# hdreader.net
KiCad netlist of a schematic drawn in EAGLE
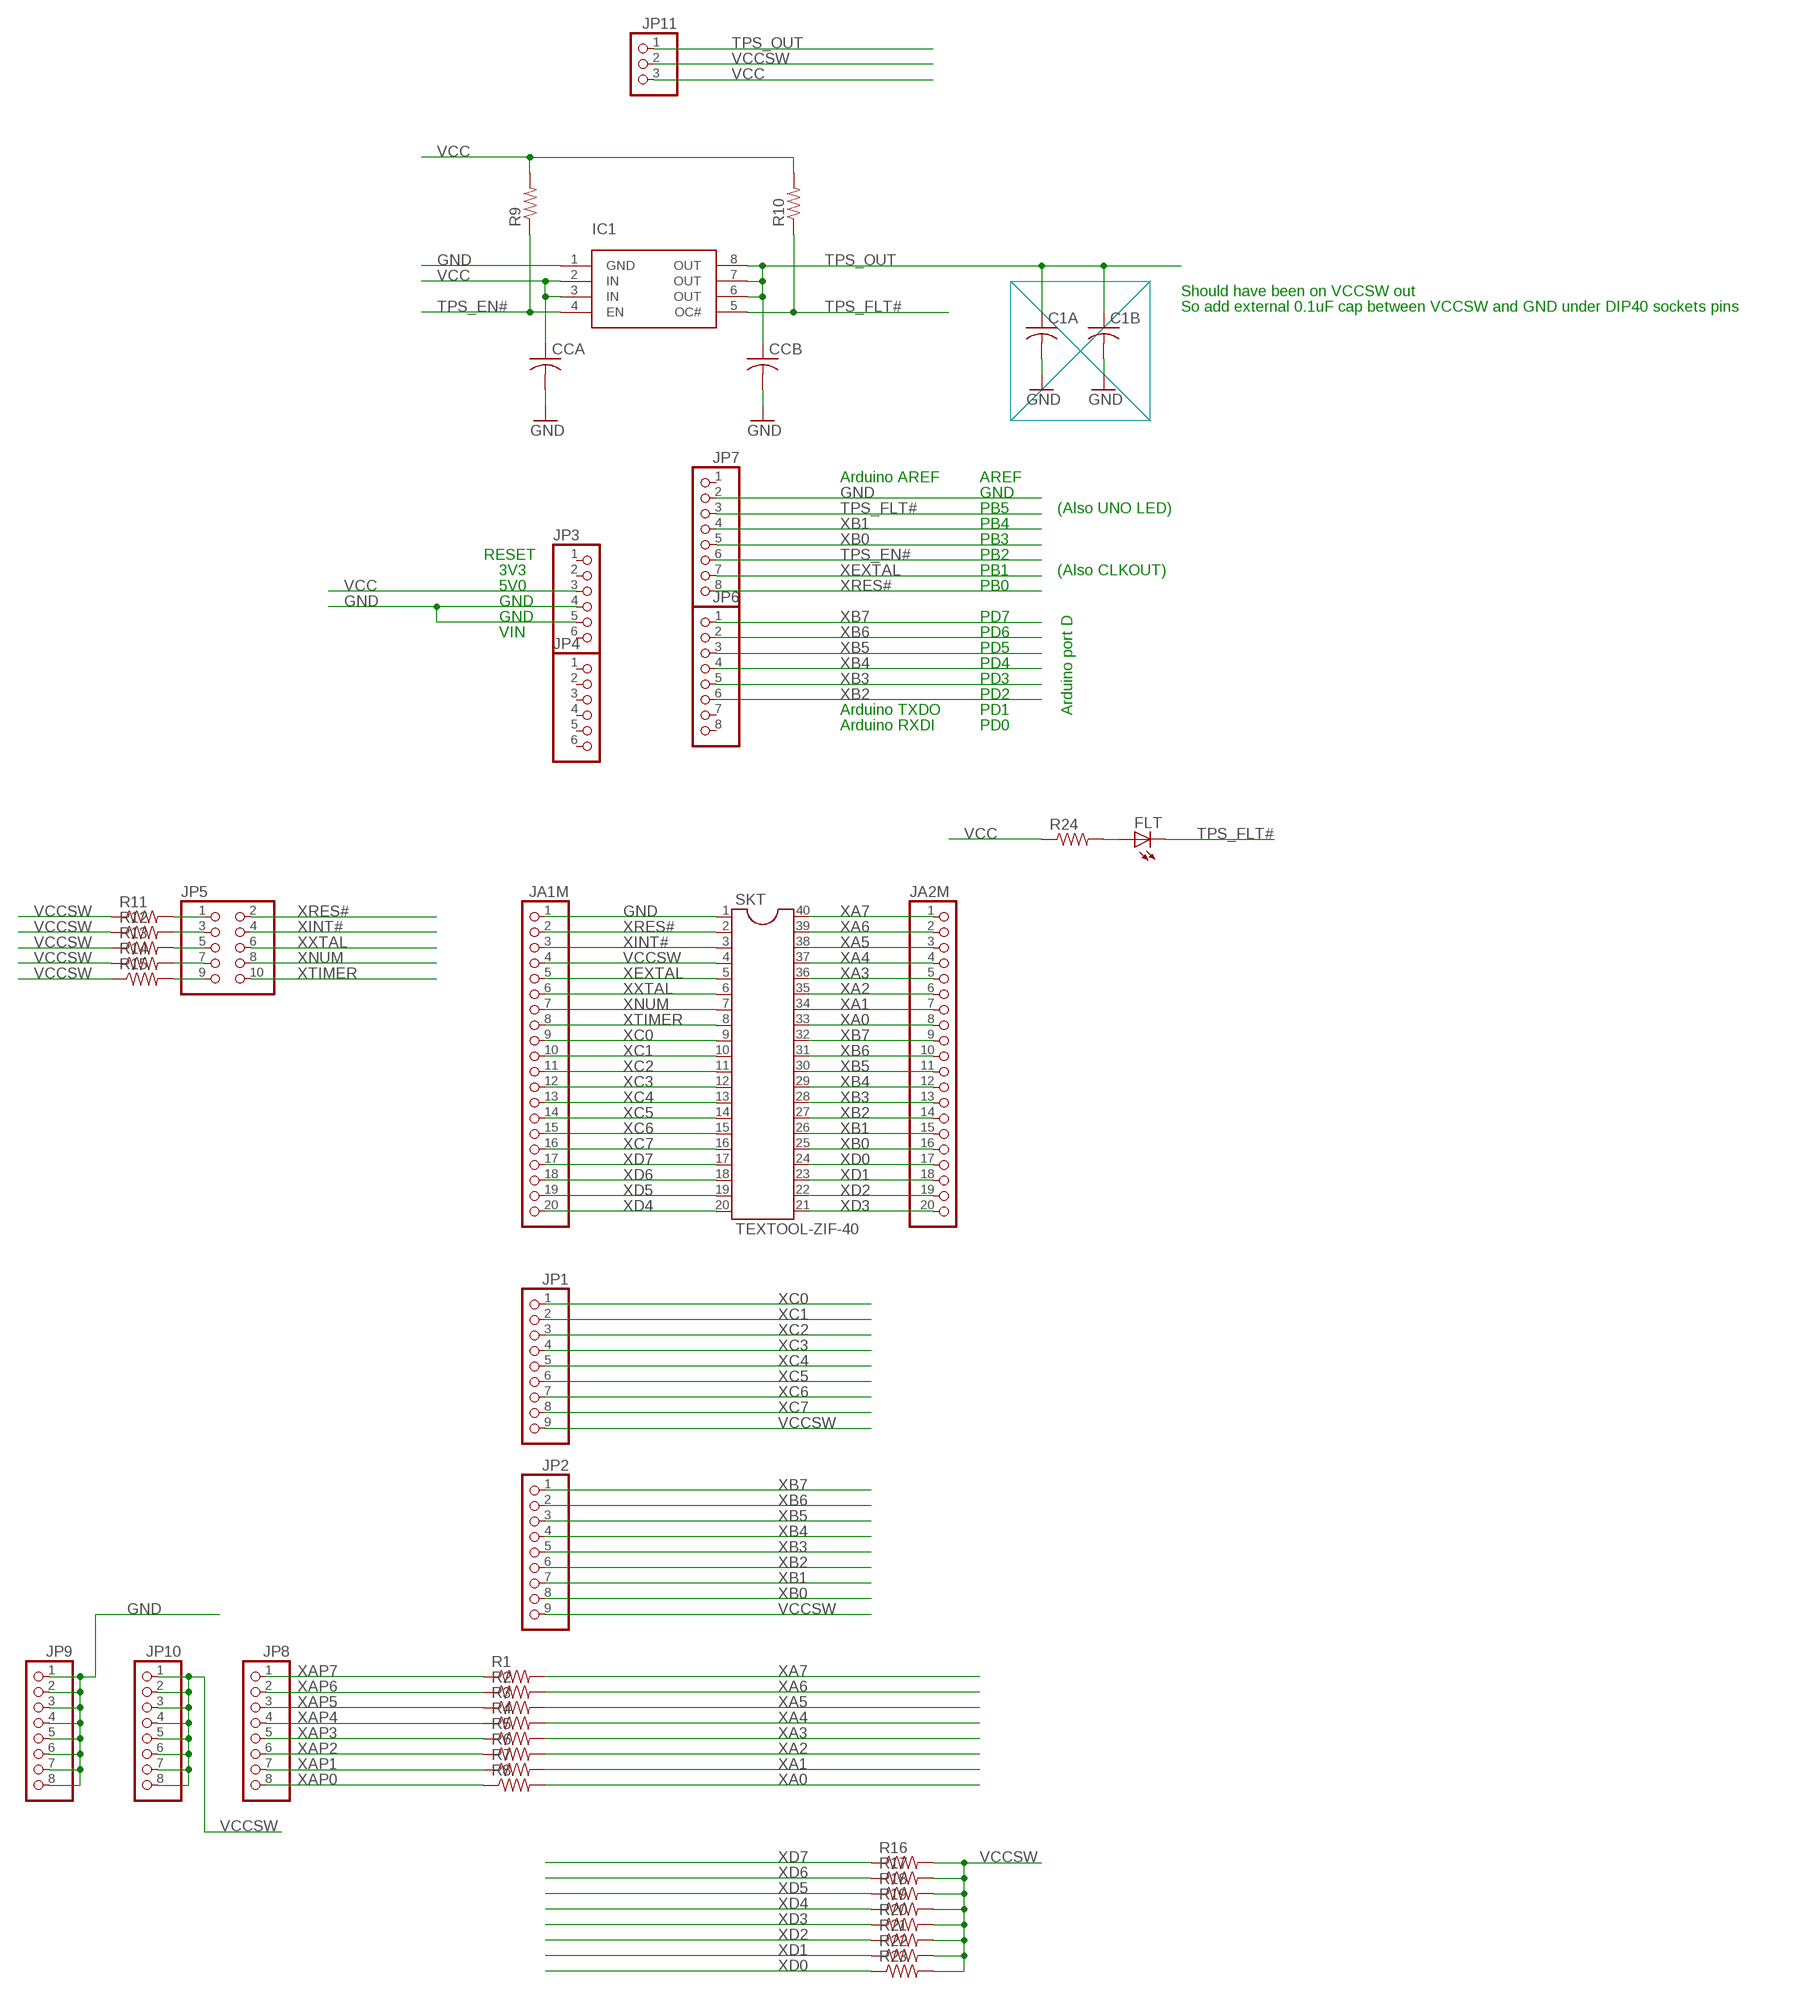
[diagram p0: schematic, sheet 1]

(export (version "E")
  (design (tool "Eeschema 10.0.6"))
  (components
    (comp (ref "C1A")
      (value "C-USC0603")
      (footprint "eagle-import:C0603")
      (libsource (lib "eagle-import") (part "C-USC0603"))
    )
    (comp (ref "C1B")
      (value "C-USC0603")
      (footprint "eagle-import:C0603")
      (libsource (lib "eagle-import") (part "C-USC0603"))
    )
    (comp (ref "CCA")
      (value "C-USC0603")
      (footprint "eagle-import:C0603")
      (libsource (lib "eagle-import") (part "C-USC0603"))
    )
    (comp (ref "CCB")
      (value "C-USC0603")
      (footprint "eagle-import:C0603")
      (libsource (lib "eagle-import") (part "C-USC0603"))
    )
    (comp (ref "FLT")
      (value "LED3MM")
      (footprint "eagle-import:LED3MM")
      (libsource (lib "eagle-import") (part "LED3MM"))
    )
    (comp (ref "IC1")
      (value "TPS2051D")
      (footprint "eagle-import:SOIC8")
      (libsource (lib "eagle-import") (part "TPS2051D"))
    )
    (comp (ref "JA1M")
      (value "PINHD-1X20")
      (footprint "eagle-import:1X20")
      (libsource (lib "eagle-import") (part "PINHD-1X20"))
    )
    (comp (ref "JA2M")
      (value "PINHD-1X20")
      (footprint "eagle-import:1X20")
      (libsource (lib "eagle-import") (part "PINHD-1X20"))
    )
    (comp (ref "JP1")
      (value "PINHD-1X9")
      (footprint "eagle-import:1X09")
      (libsource (lib "eagle-import") (part "PINHD-1X9"))
    )
    (comp (ref "JP2")
      (value "PINHD-1X9")
      (footprint "eagle-import:1X09")
      (libsource (lib "eagle-import") (part "PINHD-1X9"))
    )
    (comp (ref "JP3")
      (value "PINHD-1X6")
      (footprint "eagle-import:1X06")
      (libsource (lib "eagle-import") (part "PINHD-1X6"))
    )
    (comp (ref "JP4")
      (value "PINHD-1X6")
      (footprint "eagle-import:1X06")
      (libsource (lib "eagle-import") (part "PINHD-1X6"))
    )
    (comp (ref "JP5")
      (value "PINHD-2X5")
      (footprint "eagle-import:2X05")
      (libsource (lib "eagle-import") (part "PINHD-2X5"))
    )
    (comp (ref "JP6")
      (value "PINHD-1X8")
      (footprint "eagle-import:1X08")
      (libsource (lib "eagle-import") (part "PINHD-1X8"))
    )
    (comp (ref "JP7")
      (value "PINHD-1X8")
      (footprint "eagle-import:1X08")
      (libsource (lib "eagle-import") (part "PINHD-1X8"))
    )
    (comp (ref "JP8")
      (value "PINHD-1X8")
      (footprint "eagle-import:1X08")
      (libsource (lib "eagle-import") (part "PINHD-1X8"))
    )
    (comp (ref "JP9")
      (value "PINHD-1X8")
      (footprint "eagle-import:1X08")
      (libsource (lib "eagle-import") (part "PINHD-1X8"))
    )
    (comp (ref "JP10")
      (value "PINHD-1X8")
      (footprint "eagle-import:1X08")
      (libsource (lib "eagle-import") (part "PINHD-1X8"))
    )
    (comp (ref "JP11")
      (value "PINHD-1X3")
      (footprint "eagle-import:1X03")
      (libsource (lib "eagle-import") (part "PINHD-1X3"))
    )
    (comp (ref "R1")
      (value "R-US_R0603")
      (footprint "eagle-import:R0603")
      (libsource (lib "eagle-import") (part "R-US_R0603"))
    )
    (comp (ref "R2")
      (value "R-US_R0603")
      (footprint "eagle-import:R0603")
      (libsource (lib "eagle-import") (part "R-US_R0603"))
    )
    (comp (ref "R3")
      (value "R-US_R0603")
      (footprint "eagle-import:R0603")
      (libsource (lib "eagle-import") (part "R-US_R0603"))
    )
    (comp (ref "R4")
      (value "R-US_R0603")
      (footprint "eagle-import:R0603")
      (libsource (lib "eagle-import") (part "R-US_R0603"))
    )
    (comp (ref "R5")
      (value "R-US_R0603")
      (footprint "eagle-import:R0603")
      (libsource (lib "eagle-import") (part "R-US_R0603"))
    )
    (comp (ref "R6")
      (value "R-US_R0603")
      (footprint "eagle-import:R0603")
      (libsource (lib "eagle-import") (part "R-US_R0603"))
    )
    (comp (ref "R7")
      (value "R-US_R0603")
      (footprint "eagle-import:R0603")
      (libsource (lib "eagle-import") (part "R-US_R0603"))
    )
    (comp (ref "R8")
      (value "R-US_R0603")
      (footprint "eagle-import:R0603")
      (libsource (lib "eagle-import") (part "R-US_R0603"))
    )
    (comp (ref "R9")
      (value "R-US_R0603")
      (footprint "eagle-import:R0603")
      (libsource (lib "eagle-import") (part "R-US_R0603"))
    )
    (comp (ref "R10")
      (value "R-US_R0603")
      (footprint "eagle-import:R0603")
      (libsource (lib "eagle-import") (part "R-US_R0603"))
    )
    (comp (ref "R11")
      (value "R-US_R0603")
      (footprint "eagle-import:R0603")
      (libsource (lib "eagle-import") (part "R-US_R0603"))
    )
    (comp (ref "R12")
      (value "R-US_R0603")
      (footprint "eagle-import:R0603")
      (libsource (lib "eagle-import") (part "R-US_R0603"))
    )
    (comp (ref "R13")
      (value "R-US_R0603")
      (footprint "eagle-import:R0603")
      (libsource (lib "eagle-import") (part "R-US_R0603"))
    )
    (comp (ref "R14")
      (value "R-US_R0603")
      (footprint "eagle-import:R0603")
      (libsource (lib "eagle-import") (part "R-US_R0603"))
    )
    (comp (ref "R15")
      (value "R-US_R0603")
      (footprint "eagle-import:R0603")
      (libsource (lib "eagle-import") (part "R-US_R0603"))
    )
    (comp (ref "R16")
      (value "R-US_R0603")
      (footprint "eagle-import:R0603")
      (libsource (lib "eagle-import") (part "R-US_R0603"))
    )
    (comp (ref "R17")
      (value "R-US_R0603")
      (footprint "eagle-import:R0603")
      (libsource (lib "eagle-import") (part "R-US_R0603"))
    )
    (comp (ref "R18")
      (value "R-US_R0603")
      (footprint "eagle-import:R0603")
      (libsource (lib "eagle-import") (part "R-US_R0603"))
    )
    (comp (ref "R19")
      (value "R-US_R0603")
      (footprint "eagle-import:R0603")
      (libsource (lib "eagle-import") (part "R-US_R0603"))
    )
    (comp (ref "R20")
      (value "R-US_R0603")
      (footprint "eagle-import:R0603")
      (libsource (lib "eagle-import") (part "R-US_R0603"))
    )
    (comp (ref "R21")
      (value "R-US_R0603")
      (footprint "eagle-import:R0603")
      (libsource (lib "eagle-import") (part "R-US_R0603"))
    )
    (comp (ref "R22")
      (value "R-US_R0603")
      (footprint "eagle-import:R0603")
      (libsource (lib "eagle-import") (part "R-US_R0603"))
    )
    (comp (ref "R23")
      (value "R-US_R0603")
      (footprint "eagle-import:R0603")
      (libsource (lib "eagle-import") (part "R-US_R0603"))
    )
    (comp (ref "R24")
      (value "R-US_R0603")
      (footprint "eagle-import:R0603")
      (libsource (lib "eagle-import") (part "R-US_R0603"))
    )
    (comp (ref "SKT")
      (value "TEXTOOL-ZIF-40")
      (footprint "eagle-import:TEXTOOL-DIP-40")
      (libsource (lib "eagle-import") (part "TEXTOOL-ZIF-40"))
    )
  )
  (nets
    (net (code "1") (name "/TPS_EN#") (class "Default")
      (node (ref "IC1") (pin "4") (pinfunction "EN_4") (pintype "input"))
      (node (ref "JP7") (pin "6") (pinfunction "6_6") (pintype "passive"))
      (node (ref "R9") (pin "1") (pinfunction "1_1") (pintype "passive"))
    )
    (net (code "2") (name "/TPS_FLT#") (class "Default")
      (node (ref "FLT") (pin "K") (pinfunction "C_K") (pintype "passive"))
      (node (ref "IC1") (pin "5") (pinfunction "OC#_5") (pintype "open_collector"))
      (node (ref "JP7") (pin "3") (pinfunction "3_3") (pintype "passive"))
      (node (ref "R10") (pin "1") (pinfunction "1_1") (pintype "passive"))
    )
    (net (code "3") (name "/TPS_OUT") (class "Default")
      (node (ref "C1A") (pin "1") (pinfunction "1_1") (pintype "passive"))
      (node (ref "C1B") (pin "1") (pinfunction "1_1") (pintype "passive"))
      (node (ref "CCB") (pin "1") (pinfunction "1_1") (pintype "passive"))
      (node (ref "IC1") (pin "6") (pinfunction "OUT_6") (pintype "power_in"))
      (node (ref "IC1") (pin "7") (pinfunction "OUT_7") (pintype "power_in"))
      (node (ref "IC1") (pin "8") (pinfunction "OUT_8") (pintype "power_in"))
      (node (ref "JP11") (pin "1") (pinfunction "1_1") (pintype "passive"))
    )
    (net (code "4") (name "/VCC") (class "Default")
      (node (ref "CCA") (pin "1") (pinfunction "1_1") (pintype "passive"))
      (node (ref "IC1") (pin "2") (pinfunction "IN_2") (pintype "power_in"))
      (node (ref "IC1") (pin "3") (pinfunction "IN_3") (pintype "power_in"))
      (node (ref "JP11") (pin "3") (pinfunction "3_3") (pintype "passive"))
      (node (ref "JP3") (pin "3") (pinfunction "3_3") (pintype "passive"))
      (node (ref "R10") (pin "2") (pinfunction "2_2") (pintype "passive"))
      (node (ref "R24") (pin "1") (pinfunction "1_1") (pintype "passive"))
      (node (ref "R9") (pin "2") (pinfunction "2_2") (pintype "passive"))
    )
    (net (code "5") (name "/VCCSW") (class "Default")
      (node (ref "JA1M") (pin "4") (pinfunction "4_4") (pintype "passive"))
      (node (ref "JP1") (pin "9") (pinfunction "9_9") (pintype "passive"))
      (node (ref "JP10") (pin "1") (pinfunction "1_1") (pintype "passive"))
      (node (ref "JP10") (pin "2") (pinfunction "2_2") (pintype "passive"))
      (node (ref "JP10") (pin "3") (pinfunction "3_3") (pintype "passive"))
      (node (ref "JP10") (pin "4") (pinfunction "4_4") (pintype "passive"))
      (node (ref "JP10") (pin "5") (pinfunction "5_5") (pintype "passive"))
      (node (ref "JP10") (pin "6") (pinfunction "6_6") (pintype "passive"))
      (node (ref "JP10") (pin "7") (pinfunction "7_7") (pintype "passive"))
      (node (ref "JP10") (pin "8") (pinfunction "8_8") (pintype "passive"))
      (node (ref "JP11") (pin "2") (pinfunction "2_2") (pintype "passive"))
      (node (ref "JP2") (pin "9") (pinfunction "9_9") (pintype "passive"))
      (node (ref "R11") (pin "1") (pinfunction "1_1") (pintype "passive"))
      (node (ref "R12") (pin "1") (pinfunction "1_1") (pintype "passive"))
      (node (ref "R13") (pin "1") (pinfunction "1_1") (pintype "passive"))
      (node (ref "R14") (pin "1") (pinfunction "1_1") (pintype "passive"))
      (node (ref "R15") (pin "1") (pinfunction "1_1") (pintype "passive"))
      (node (ref "R16") (pin "2") (pinfunction "2_2") (pintype "passive"))
      (node (ref "R17") (pin "2") (pinfunction "2_2") (pintype "passive"))
      (node (ref "R18") (pin "2") (pinfunction "2_2") (pintype "passive"))
      (node (ref "R19") (pin "2") (pinfunction "2_2") (pintype "passive"))
      (node (ref "R20") (pin "2") (pinfunction "2_2") (pintype "passive"))
      (node (ref "R21") (pin "2") (pinfunction "2_2") (pintype "passive"))
      (node (ref "R22") (pin "2") (pinfunction "2_2") (pintype "passive"))
      (node (ref "R23") (pin "2") (pinfunction "2_2") (pintype "passive"))
      (node (ref "SKT") (pin "4") (pinfunction "4_4") (pintype "passive"))
    )
    (net (code "6") (name "/XA0") (class "Default")
      (node (ref "JA2M") (pin "8") (pinfunction "8_8") (pintype "passive"))
      (node (ref "R8") (pin "2") (pinfunction "2_2") (pintype "passive"))
      (node (ref "SKT") (pin "33") (pinfunction "33_33") (pintype "passive"))
    )
    (net (code "7") (name "/XA1") (class "Default")
      (node (ref "JA2M") (pin "7") (pinfunction "7_7") (pintype "passive"))
      (node (ref "R7") (pin "2") (pinfunction "2_2") (pintype "passive"))
      (node (ref "SKT") (pin "34") (pinfunction "34_34") (pintype "passive"))
    )
    (net (code "8") (name "/XA2") (class "Default")
      (node (ref "JA2M") (pin "6") (pinfunction "6_6") (pintype "passive"))
      (node (ref "R6") (pin "2") (pinfunction "2_2") (pintype "passive"))
      (node (ref "SKT") (pin "35") (pinfunction "35_35") (pintype "passive"))
    )
    (net (code "9") (name "/XA3") (class "Default")
      (node (ref "JA2M") (pin "5") (pinfunction "5_5") (pintype "passive"))
      (node (ref "R5") (pin "2") (pinfunction "2_2") (pintype "passive"))
      (node (ref "SKT") (pin "36") (pinfunction "36_36") (pintype "passive"))
    )
    (net (code "10") (name "/XA4") (class "Default")
      (node (ref "JA2M") (pin "4") (pinfunction "4_4") (pintype "passive"))
      (node (ref "R4") (pin "2") (pinfunction "2_2") (pintype "passive"))
      (node (ref "SKT") (pin "37") (pinfunction "37_37") (pintype "passive"))
    )
    (net (code "11") (name "/XA5") (class "Default")
      (node (ref "JA2M") (pin "3") (pinfunction "3_3") (pintype "passive"))
      (node (ref "R3") (pin "2") (pinfunction "2_2") (pintype "passive"))
      (node (ref "SKT") (pin "38") (pinfunction "38_38") (pintype "passive"))
    )
    (net (code "12") (name "/XA6") (class "Default")
      (node (ref "JA2M") (pin "2") (pinfunction "2_2") (pintype "passive"))
      (node (ref "R2") (pin "2") (pinfunction "2_2") (pintype "passive"))
      (node (ref "SKT") (pin "39") (pinfunction "39_39") (pintype "passive"))
    )
    (net (code "13") (name "/XA7") (class "Default")
      (node (ref "JA2M") (pin "1") (pinfunction "1_1") (pintype "passive"))
      (node (ref "R1") (pin "2") (pinfunction "2_2") (pintype "passive"))
      (node (ref "SKT") (pin "40") (pinfunction "40_40") (pintype "passive"))
    )
    (net (code "14") (name "/XAP0") (class "Default")
      (node (ref "JP8") (pin "8") (pinfunction "8_8") (pintype "passive"))
      (node (ref "R8") (pin "1") (pinfunction "1_1") (pintype "passive"))
    )
    (net (code "15") (name "/XAP1") (class "Default")
      (node (ref "JP8") (pin "7") (pinfunction "7_7") (pintype "passive"))
      (node (ref "R7") (pin "1") (pinfunction "1_1") (pintype "passive"))
    )
    (net (code "16") (name "/XAP2") (class "Default")
      (node (ref "JP8") (pin "6") (pinfunction "6_6") (pintype "passive"))
      (node (ref "R6") (pin "1") (pinfunction "1_1") (pintype "passive"))
    )
    (net (code "17") (name "/XAP3") (class "Default")
      (node (ref "JP8") (pin "5") (pinfunction "5_5") (pintype "passive"))
      (node (ref "R5") (pin "1") (pinfunction "1_1") (pintype "passive"))
    )
    (net (code "18") (name "/XAP4") (class "Default")
      (node (ref "JP8") (pin "4") (pinfunction "4_4") (pintype "passive"))
      (node (ref "R4") (pin "1") (pinfunction "1_1") (pintype "passive"))
    )
    (net (code "19") (name "/XAP5") (class "Default")
      (node (ref "JP8") (pin "3") (pinfunction "3_3") (pintype "passive"))
      (node (ref "R3") (pin "1") (pinfunction "1_1") (pintype "passive"))
    )
    (net (code "20") (name "/XAP6") (class "Default")
      (node (ref "JP8") (pin "2") (pinfunction "2_2") (pintype "passive"))
      (node (ref "R2") (pin "1") (pinfunction "1_1") (pintype "passive"))
    )
    (net (code "21") (name "/XAP7") (class "Default")
      (node (ref "JP8") (pin "1") (pinfunction "1_1") (pintype "passive"))
      (node (ref "R1") (pin "1") (pinfunction "1_1") (pintype "passive"))
    )
    (net (code "22") (name "/XB0") (class "Default")
      (node (ref "JA2M") (pin "16") (pinfunction "16_16") (pintype "passive"))
      (node (ref "JP2") (pin "8") (pinfunction "8_8") (pintype "passive"))
      (node (ref "JP7") (pin "5") (pinfunction "5_5") (pintype "passive"))
      (node (ref "SKT") (pin "25") (pinfunction "25_25") (pintype "passive"))
    )
    (net (code "23") (name "/XB1") (class "Default")
      (node (ref "JA2M") (pin "15") (pinfunction "15_15") (pintype "passive"))
      (node (ref "JP2") (pin "7") (pinfunction "7_7") (pintype "passive"))
      (node (ref "JP7") (pin "4") (pinfunction "4_4") (pintype "passive"))
      (node (ref "SKT") (pin "26") (pinfunction "26_26") (pintype "passive"))
    )
    (net (code "24") (name "/XB2") (class "Default")
      (node (ref "JA2M") (pin "14") (pinfunction "14_14") (pintype "passive"))
      (node (ref "JP2") (pin "6") (pinfunction "6_6") (pintype "passive"))
      (node (ref "JP6") (pin "6") (pinfunction "6_6") (pintype "passive"))
      (node (ref "SKT") (pin "27") (pinfunction "27_27") (pintype "passive"))
    )
    (net (code "25") (name "/XB3") (class "Default")
      (node (ref "JA2M") (pin "13") (pinfunction "13_13") (pintype "passive"))
      (node (ref "JP2") (pin "5") (pinfunction "5_5") (pintype "passive"))
      (node (ref "JP6") (pin "5") (pinfunction "5_5") (pintype "passive"))
      (node (ref "SKT") (pin "28") (pinfunction "28_28") (pintype "passive"))
    )
    (net (code "26") (name "/XB4") (class "Default")
      (node (ref "JA2M") (pin "12") (pinfunction "12_12") (pintype "passive"))
      (node (ref "JP2") (pin "4") (pinfunction "4_4") (pintype "passive"))
      (node (ref "JP6") (pin "4") (pinfunction "4_4") (pintype "passive"))
      (node (ref "SKT") (pin "29") (pinfunction "29_29") (pintype "passive"))
    )
    (net (code "27") (name "/XB5") (class "Default")
      (node (ref "JA2M") (pin "11") (pinfunction "11_11") (pintype "passive"))
      (node (ref "JP2") (pin "3") (pinfunction "3_3") (pintype "passive"))
      (node (ref "JP6") (pin "3") (pinfunction "3_3") (pintype "passive"))
      (node (ref "SKT") (pin "30") (pinfunction "30_30") (pintype "passive"))
    )
    (net (code "28") (name "/XB6") (class "Default")
      (node (ref "JA2M") (pin "10") (pinfunction "10_10") (pintype "passive"))
      (node (ref "JP2") (pin "2") (pinfunction "2_2") (pintype "passive"))
      (node (ref "JP6") (pin "2") (pinfunction "2_2") (pintype "passive"))
      (node (ref "SKT") (pin "31") (pinfunction "31_31") (pintype "passive"))
    )
    (net (code "29") (name "/XB7") (class "Default")
      (node (ref "JA2M") (pin "9") (pinfunction "9_9") (pintype "passive"))
      (node (ref "JP2") (pin "1") (pinfunction "1_1") (pintype "passive"))
      (node (ref "JP6") (pin "1") (pinfunction "1_1") (pintype "passive"))
      (node (ref "SKT") (pin "32") (pinfunction "32_32") (pintype "passive"))
    )
    (net (code "30") (name "/XC0") (class "Default")
      (node (ref "JA1M") (pin "9") (pinfunction "9_9") (pintype "passive"))
      (node (ref "JP1") (pin "1") (pinfunction "1_1") (pintype "passive"))
      (node (ref "SKT") (pin "9") (pinfunction "9_9") (pintype "passive"))
    )
    (net (code "31") (name "/XC1") (class "Default")
      (node (ref "JA1M") (pin "10") (pinfunction "10_10") (pintype "passive"))
      (node (ref "JP1") (pin "2") (pinfunction "2_2") (pintype "passive"))
      (node (ref "SKT") (pin "10") (pinfunction "10_10") (pintype "passive"))
    )
    (net (code "32") (name "/XC2") (class "Default")
      (node (ref "JA1M") (pin "11") (pinfunction "11_11") (pintype "passive"))
      (node (ref "JP1") (pin "3") (pinfunction "3_3") (pintype "passive"))
      (node (ref "SKT") (pin "11") (pinfunction "11_11") (pintype "passive"))
    )
    (net (code "33") (name "/XC3") (class "Default")
      (node (ref "JA1M") (pin "12") (pinfunction "12_12") (pintype "passive"))
      (node (ref "JP1") (pin "4") (pinfunction "4_4") (pintype "passive"))
      (node (ref "SKT") (pin "12") (pinfunction "12_12") (pintype "passive"))
    )
    (net (code "34") (name "/XC4") (class "Default")
      (node (ref "JA1M") (pin "13") (pinfunction "13_13") (pintype "passive"))
      (node (ref "JP1") (pin "5") (pinfunction "5_5") (pintype "passive"))
      (node (ref "SKT") (pin "13") (pinfunction "13_13") (pintype "passive"))
    )
    (net (code "35") (name "/XC5") (class "Default")
      (node (ref "JA1M") (pin "14") (pinfunction "14_14") (pintype "passive"))
      (node (ref "JP1") (pin "6") (pinfunction "6_6") (pintype "passive"))
      (node (ref "SKT") (pin "14") (pinfunction "14_14") (pintype "passive"))
    )
    (net (code "36") (name "/XC6") (class "Default")
      (node (ref "JA1M") (pin "15") (pinfunction "15_15") (pintype "passive"))
      (node (ref "JP1") (pin "7") (pinfunction "7_7") (pintype "passive"))
      (node (ref "SKT") (pin "15") (pinfunction "15_15") (pintype "passive"))
    )
    (net (code "37") (name "/XC7") (class "Default")
      (node (ref "JA1M") (pin "16") (pinfunction "16_16") (pintype "passive"))
      (node (ref "JP1") (pin "8") (pinfunction "8_8") (pintype "passive"))
      (node (ref "SKT") (pin "16") (pinfunction "16_16") (pintype "passive"))
    )
    (net (code "38") (name "/XD0") (class "Default")
      (node (ref "JA2M") (pin "17") (pinfunction "17_17") (pintype "passive"))
      (node (ref "R23") (pin "1") (pinfunction "1_1") (pintype "passive"))
      (node (ref "SKT") (pin "24") (pinfunction "24_24") (pintype "passive"))
    )
    (net (code "39") (name "/XD1") (class "Default")
      (node (ref "JA2M") (pin "18") (pinfunction "18_18") (pintype "passive"))
      (node (ref "R22") (pin "1") (pinfunction "1_1") (pintype "passive"))
      (node (ref "SKT") (pin "23") (pinfunction "23_23") (pintype "passive"))
    )
    (net (code "40") (name "/XD2") (class "Default")
      (node (ref "JA2M") (pin "19") (pinfunction "19_19") (pintype "passive"))
      (node (ref "R21") (pin "1") (pinfunction "1_1") (pintype "passive"))
      (node (ref "SKT") (pin "22") (pinfunction "22_22") (pintype "passive"))
    )
    (net (code "41") (name "/XD3") (class "Default")
      (node (ref "JA2M") (pin "20") (pinfunction "20_20") (pintype "passive"))
      (node (ref "R20") (pin "1") (pinfunction "1_1") (pintype "passive"))
      (node (ref "SKT") (pin "21") (pinfunction "21_21") (pintype "passive"))
    )
    (net (code "42") (name "/XD4") (class "Default")
      (node (ref "JA1M") (pin "20") (pinfunction "20_20") (pintype "passive"))
      (node (ref "R19") (pin "1") (pinfunction "1_1") (pintype "passive"))
      (node (ref "SKT") (pin "20") (pinfunction "20_20") (pintype "passive"))
    )
    (net (code "43") (name "/XD5") (class "Default")
      (node (ref "JA1M") (pin "19") (pinfunction "19_19") (pintype "passive"))
      (node (ref "R18") (pin "1") (pinfunction "1_1") (pintype "passive"))
      (node (ref "SKT") (pin "19") (pinfunction "19_19") (pintype "passive"))
    )
    (net (code "44") (name "/XD6") (class "Default")
      (node (ref "JA1M") (pin "18") (pinfunction "18_18") (pintype "passive"))
      (node (ref "R17") (pin "1") (pinfunction "1_1") (pintype "passive"))
      (node (ref "SKT") (pin "18") (pinfunction "18_18") (pintype "passive"))
    )
    (net (code "45") (name "/XD7") (class "Default")
      (node (ref "JA1M") (pin "17") (pinfunction "17_17") (pintype "passive"))
      (node (ref "R16") (pin "1") (pinfunction "1_1") (pintype "passive"))
      (node (ref "SKT") (pin "17") (pinfunction "17_17") (pintype "passive"))
    )
    (net (code "46") (name "/XEXTAL") (class "Default")
      (node (ref "JA1M") (pin "5") (pinfunction "5_5") (pintype "passive"))
      (node (ref "JP7") (pin "7") (pinfunction "7_7") (pintype "passive"))
      (node (ref "SKT") (pin "5") (pinfunction "5_5") (pintype "passive"))
    )
    (net (code "47") (name "/XINT#") (class "Default")
      (node (ref "JA1M") (pin "3") (pinfunction "3_3") (pintype "passive"))
      (node (ref "JP5") (pin "4") (pinfunction "4_4") (pintype "passive"))
      (node (ref "SKT") (pin "3") (pinfunction "3_3") (pintype "passive"))
    )
    (net (code "48") (name "/XNUM") (class "Default")
      (node (ref "JA1M") (pin "7") (pinfunction "7_7") (pintype "passive"))
      (node (ref "JP5") (pin "8") (pinfunction "8_8") (pintype "passive"))
      (node (ref "SKT") (pin "7") (pinfunction "7_7") (pintype "passive"))
    )
    (net (code "49") (name "/XRES#") (class "Default")
      (node (ref "JA1M") (pin "2") (pinfunction "2_2") (pintype "passive"))
      (node (ref "JP5") (pin "2") (pinfunction "2_2") (pintype "passive"))
      (node (ref "JP7") (pin "8") (pinfunction "8_8") (pintype "passive"))
      (node (ref "SKT") (pin "2") (pinfunction "2_2") (pintype "passive"))
    )
    (net (code "50") (name "/XTIMER") (class "Default")
      (node (ref "JA1M") (pin "8") (pinfunction "8_8") (pintype "passive"))
      (node (ref "JP5") (pin "10") (pinfunction "10_10") (pintype "passive"))
      (node (ref "SKT") (pin "8") (pinfunction "8_8") (pintype "passive"))
    )
    (net (code "51") (name "/XXTAL") (class "Default")
      (node (ref "JA1M") (pin "6") (pinfunction "6_6") (pintype "passive"))
      (node (ref "JP5") (pin "6") (pinfunction "6_6") (pintype "passive"))
      (node (ref "SKT") (pin "6") (pinfunction "6_6") (pintype "passive"))
    )
    (net (code "52") (name "GND") (class "Default")
      (node (ref "C1A") (pin "2") (pinfunction "2_2") (pintype "passive"))
      (node (ref "C1B") (pin "2") (pinfunction "2_2") (pintype "passive"))
      (node (ref "CCA") (pin "2") (pinfunction "2_2") (pintype "passive"))
      (node (ref "CCB") (pin "2") (pinfunction "2_2") (pintype "passive"))
      (node (ref "IC1") (pin "1") (pinfunction "GND_1") (pintype "power_in"))
      (node (ref "JA1M") (pin "1") (pinfunction "1_1") (pintype "passive"))
      (node (ref "JP3") (pin "4") (pinfunction "4_4") (pintype "passive"))
      (node (ref "JP3") (pin "5") (pinfunction "5_5") (pintype "passive"))
      (node (ref "JP7") (pin "2") (pinfunction "2_2") (pintype "passive"))
      (node (ref "JP9") (pin "1") (pinfunction "1_1") (pintype "passive"))
      (node (ref "JP9") (pin "2") (pinfunction "2_2") (pintype "passive"))
      (node (ref "JP9") (pin "3") (pinfunction "3_3") (pintype "passive"))
      (node (ref "JP9") (pin "4") (pinfunction "4_4") (pintype "passive"))
      (node (ref "JP9") (pin "5") (pinfunction "5_5") (pintype "passive"))
      (node (ref "JP9") (pin "6") (pinfunction "6_6") (pintype "passive"))
      (node (ref "JP9") (pin "7") (pinfunction "7_7") (pintype "passive"))
      (node (ref "JP9") (pin "8") (pinfunction "8_8") (pintype "passive"))
      (node (ref "SKT") (pin "1") (pinfunction "1_1") (pintype "passive"))
    )
    (net (code "53") (name "Net-(FLT-PadA)") (class "Default")
      (node (ref "FLT") (pin "A") (pinfunction "A_A") (pintype "passive"))
      (node (ref "R24") (pin "2") (pinfunction "2_2") (pintype "passive"))
    )
    (net (code "54") (name "Net-(JP5-Pad1)") (class "Default")
      (node (ref "JP5") (pin "1") (pinfunction "1_1") (pintype "passive"))
      (node (ref "R11") (pin "2") (pinfunction "2_2") (pintype "passive"))
    )
    (net (code "55") (name "Net-(JP5-Pad3)") (class "Default")
      (node (ref "JP5") (pin "3") (pinfunction "3_3") (pintype "passive"))
      (node (ref "R12") (pin "2") (pinfunction "2_2") (pintype "passive"))
    )
    (net (code "56") (name "Net-(JP5-Pad5)") (class "Default")
      (node (ref "JP5") (pin "5") (pinfunction "5_5") (pintype "passive"))
      (node (ref "R13") (pin "2") (pinfunction "2_2") (pintype "passive"))
    )
    (net (code "57") (name "Net-(JP5-Pad7)") (class "Default")
      (node (ref "JP5") (pin "7") (pinfunction "7_7") (pintype "passive"))
      (node (ref "R14") (pin "2") (pinfunction "2_2") (pintype "passive"))
    )
    (net (code "58") (name "Net-(JP5-Pad9)") (class "Default")
      (node (ref "JP5") (pin "9") (pinfunction "9_9") (pintype "passive"))
      (node (ref "R15") (pin "2") (pinfunction "2_2") (pintype "passive"))
    )
    (net (code "59") (name "unconnected-(JP3-Pad1)") (class "Default")
      (node (ref "JP3") (pin "1") (pinfunction "1_1") (pintype "passive"))
    )
    (net (code "60") (name "unconnected-(JP3-Pad2)") (class "Default")
      (node (ref "JP3") (pin "2") (pinfunction "2_2") (pintype "passive"))
    )
    (net (code "61") (name "unconnected-(JP3-Pad6)") (class "Default")
      (node (ref "JP3") (pin "6") (pinfunction "6_6") (pintype "passive"))
    )
    (net (code "62") (name "unconnected-(JP4-Pad1)") (class "Default")
      (node (ref "JP4") (pin "1") (pinfunction "1_1") (pintype "passive"))
    )
    (net (code "63") (name "unconnected-(JP4-Pad2)") (class "Default")
      (node (ref "JP4") (pin "2") (pinfunction "2_2") (pintype "passive"))
    )
    (net (code "64") (name "unconnected-(JP4-Pad3)") (class "Default")
      (node (ref "JP4") (pin "3") (pinfunction "3_3") (pintype "passive"))
    )
    (net (code "65") (name "unconnected-(JP4-Pad4)") (class "Default")
      (node (ref "JP4") (pin "4") (pinfunction "4_4") (pintype "passive"))
    )
    (net (code "66") (name "unconnected-(JP4-Pad5)") (class "Default")
      (node (ref "JP4") (pin "5") (pinfunction "5_5") (pintype "passive"))
    )
    (net (code "67") (name "unconnected-(JP4-Pad6)") (class "Default")
      (node (ref "JP4") (pin "6") (pinfunction "6_6") (pintype "passive"))
    )
    (net (code "68") (name "unconnected-(JP6-Pad7)") (class "Default")
      (node (ref "JP6") (pin "7") (pinfunction "7_7") (pintype "passive"))
    )
    (net (code "69") (name "unconnected-(JP6-Pad8)") (class "Default")
      (node (ref "JP6") (pin "8") (pinfunction "8_8") (pintype "passive"))
    )
    (net (code "70") (name "unconnected-(JP7-Pad1)") (class "Default")
      (node (ref "JP7") (pin "1") (pinfunction "1_1") (pintype "passive"))
    )
  )
)
